# 7_High_Voltage.net
KiCad netlist of a schematic drawn in Altium Designer
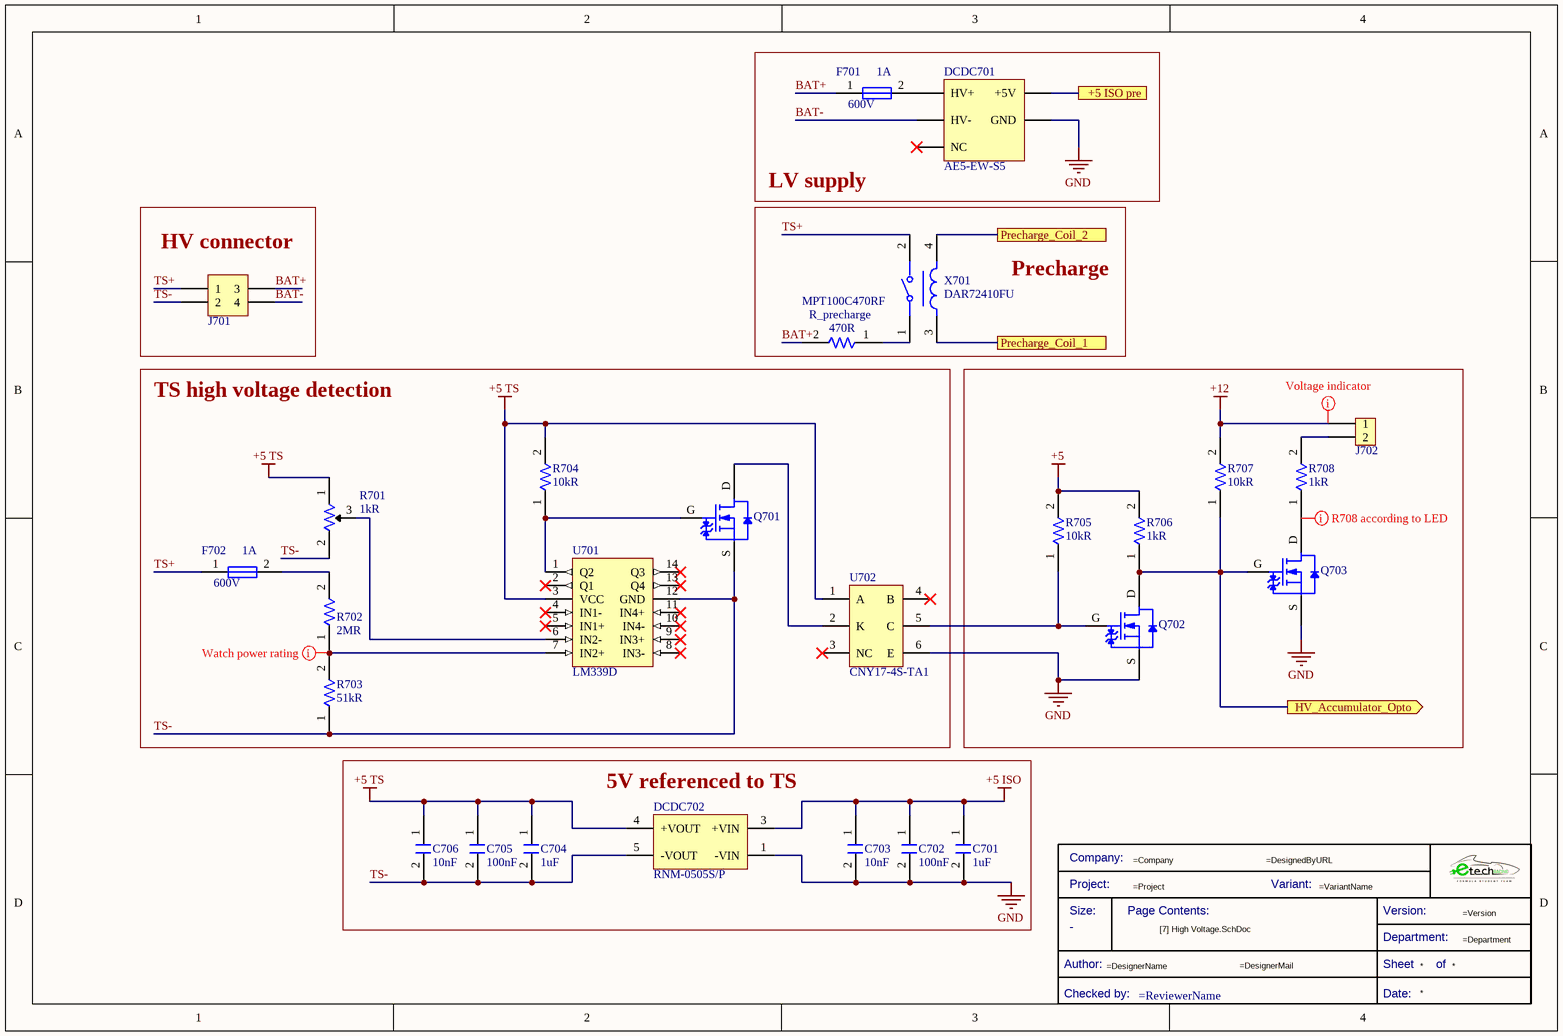
[diagram p0: [7] High Voltage.SchDoc]

(export (version "E")
  (design (tool "Eeschema 10.0.6"))
  (components
    (comp (ref "*")
      (value "Title Block_template")
      (description "Standard Title Block")
      (fields (field (name "SIZE") "-"))
      (libsource (lib "e-Tech_Racing") (part "Title Block_template"))
    )
    (comp (ref "C701")
      (value "885012207103")
      (footprint "C0805FNPC-R")
      (fields
        (field (name "TOLERANCE") "10%")
        (field (name "CAPACITANCE") "1uF")
        (field (name ".CREATOR") "GP")
      )
      (libsource (lib "Passives") (part "C1u-50V-0805FNPC-X7R"))
    )
    (comp (ref "C702")
      (value "885012207098")
      (footprint "C0805FNPC-R")
      (description "Cap, 0.1ΜF, 50V, 10%, X7R, 0805")
      (fields
        (field (name "TOLERANCE") "10%")
        (field (name "CAPACITANCE") "100nF")
        (field (name ".CREATOR") "DR")
      )
      (libsource (lib "Passives") (part "C100n-50V-0805FNPC-X7R"))
    )
    (comp (ref "C703")
      (value "885012207092")
      (footprint "C0805FNPC-R")
      (description "Cap, 0.01ΜF, 50V, 10%, X7R, 0805")
      (fields
        (field (name "TOLERANCE") "10%")
        (field (name "CAPACITANCE") "10nF")
        (field (name ".CREATOR") "DR")
      )
      (libsource (lib "Passives") (part "C10n-50V-0805FNPC-X7R"))
    )
    (comp (ref "C704")
      (value "885012207103")
      (footprint "C0805FNPC-R")
      (fields
        (field (name "TOLERANCE") "10%")
        (field (name "CAPACITANCE") "1uF")
        (field (name ".CREATOR") "GP")
      )
      (libsource (lib "Passives") (part "C1u-50V-0805FNPC-X7R"))
    )
    (comp (ref "C705")
      (value "885012207098")
      (footprint "C0805FNPC-R")
      (description "Cap, 0.1ΜF, 50V, 10%, X7R, 0805")
      (fields
        (field (name "TOLERANCE") "10%")
        (field (name "CAPACITANCE") "100nF")
        (field (name ".CREATOR") "DR")
      )
      (libsource (lib "Passives") (part "C100n-50V-0805FNPC-X7R"))
    )
    (comp (ref "C706")
      (value "885012207092")
      (footprint "C0805FNPC-R")
      (description "Cap, 0.01ΜF, 50V, 10%, X7R, 0805")
      (fields
        (field (name "TOLERANCE") "10%")
        (field (name "CAPACITANCE") "10nF")
        (field (name ".CREATOR") "DR")
      )
      (libsource (lib "Passives") (part "C10n-50V-0805FNPC-X7R"))
    )
    (comp (ref "DCDC701")
      (value "AE5-EW-S5")
      (footprint "DCDC_1000-5_ISO")
      (description "dc-dc isolated, 5 W, 100~1000 Vdc input, 5V, 1 A, DIP, ext temp")
      (fields (field (name "MANUFACTURER PART NUMBER 1") "AE5-EW-S5") (field (name ".CREATOR") "DR"))
      (libsource (lib "Semiconductor") (part "DCDC-ISO-1000V/5V-1A"))
    )
    (comp (ref "DCDC702")
      (value "RNM-0505S/P")
      (footprint "DCDC_RNM-0505S/P")
      (description "1W DC/DC-Converter 'ECONOLINE' DIP6 1kV unreg; V. In: 05; V. Out: 05; mA. Out: 200")
      (fields
        (field (name "MANUFACTURER") "Recom")
        (field (name "MANUFACTURER PART NUMBER") "RNM-0505S/P")
        (field (name ".CREATOR") "GP")
      )
      (libsource (lib "Semiconductor") (part "DCDC_RNM-0505S/P"))
    )
    (comp (ref "F701")
      (value "485001")
      (footprint "Fuse_485001")
      (description "Surface Mount Fuses 600V 1A Fast Acting")
      (fields
        (field (name "VOLTAGE RATING (DC)") "600V")
        (field (name "CURRENT RATING") "1A")
        (field (name ".CREATOR") "DO")
      )
      (libsource (lib "Filter components") (part "Fuse_1A_600V"))
    )
    (comp (ref "F702")
      (value "485001")
      (footprint "Fuse_485001")
      (description "Surface Mount Fuses 600V 1A Fast Acting")
      (fields
        (field (name "VOLTAGE RATING (DC)") "600V")
        (field (name "CURRENT RATING") "1A")
        (field (name ".CREATOR") "DO")
      )
      (libsource (lib "Filter components") (part "Fuse_1A_600V"))
    )
    (comp (ref "J701")
      (value "430450412")
      (footprint "J_MicroFit_2x2_v")
      (description "Header 2 Row Vertical Polarizing Peg 4 Pin Tin Plate SMT/Glow Wire Kinked Leads")
      (fields (field (name ".CREATOR") "DR"))
      (libsource (lib "Electromechanical") (part "J_MicroFit_2x2"))
    )
    (comp (ref "J702")
      (value "282836-2")
      (footprint "J_screw_1x2")
      (description "Connector, Terminal Block; Wire Receptacle; 2 Pos.; 16-30 AWG; 0.197 in. CL; Sid")
      (libsource (lib "Electromechanical") (part "J_CON2x1"))
    )
    (comp (ref "Q701")
      (value "CPH3455-TL-H")
      (footprint "TRT-NCH-3/35-CPH")
      (description "CPH3455-TL-H N-channel MOSFET Transistor; 3 A; 35 V; 3-Pin CPH")
      (fields (field (name "MANUFACTURER") "ON Semiconductor") (field (name ".CREATOR") "GP"))
      (libsource (lib "Semiconductor") (part "TRT-NCH-3/35-CPH"))
    )
    (comp (ref "Q702")
      (value "CPH3455-TL-H")
      (footprint "TRT-NCH-3/35-CPH")
      (description "CPH3455-TL-H N-channel MOSFET Transistor; 3 A; 35 V; 3-Pin CPH")
      (fields (field (name "MANUFACTURER") "ON Semiconductor") (field (name ".CREATOR") "GP"))
      (libsource (lib "Semiconductor") (part "TRT-NCH-3/35-CPH"))
    )
    (comp (ref "Q703")
      (value "CPH3455-TL-H")
      (footprint "TRT-NCH-3/35-CPH")
      (description "CPH3455-TL-H N-channel MOSFET Transistor; 3 A; 35 V; 3-Pin CPH")
      (fields (field (name "MANUFACTURER") "ON Semiconductor") (field (name ".CREATOR") "GP"))
      (libsource (lib "Semiconductor") (part "TRT-NCH-3/35-CPH"))
    )
    (comp (ref "R701")
      (value "3296Y-1-102LF")
      (footprint "R1k-VTR")
      (description "Res Cermet Trimmer 1K Ohm 10% 1/2W 25(Elec)Turn 2.19mm (9.53 X 4.83 X 11.55mm) Pin Thru-Hole Tube")
      (fields
        (field (name "MANUFACTURER") "Bourns")
        (field (name "TOLERANCE") "10%")
        (field (name "RESISTANCE") "1kR")
        (field (name ".CREATOR") "DO")
      )
      (libsource (lib "Passives") (part "R1k-VTR"))
    )
    (comp (ref "R702")
      (value "HVC1206-2M0FT3")
      (footprint "R1206FTK-W")
      (description "Res Thick Film 1206 2M Ohm 1% 0.3W ±100ppm/C Pad SMD T/R")
      (fields
        (field (name "MANUFACTURER") "TT Welwyn")
        (field (name "TOLERANCE") "1%")
        (field (name "RESISTENCE") "2MR")
        (field (name ".CREATOR") "DO")
      )
      (libsource (lib "Passives") (part "R2M-1206FTK"))
    )
    (comp (ref "R703")
      (value "CRCW120610K0FKEA")
      (footprint "R1206FTK-W")
      (description "Res Thick Film 1206 51K Ohm 1% 1/4W ±100ppm/°C Molded SMD SMD Punched Carrier T/R")
      (fields
        (field (name "MANUFACTURER") "Panasonic")
        (field (name "MANUFACTURER PART NUMBER") "ERJ-S08F5102V")
        (field (name "RESISTANCE") "51kR")
        (field (name ".CREATOR") "DO")
      )
      (libsource (lib "Passives") (part "R51k-1206FTK"))
    )
    (comp (ref "R704")
      (value "CR0805-JW-103ELF")
      (footprint "R0805FTK")
      (fields
        (field (name "TOLERANCE") "5%")
        (field (name "RESISTANCE") "10kR")
        (field (name ".CREATOR") "DR")
      )
      (libsource (lib "Passives") (part "R10k-0805FTK"))
    )
    (comp (ref "R705")
      (value "CR0805-JW-103ELF")
      (footprint "R0805FTK")
      (fields
        (field (name "TOLERANCE") "5%")
        (field (name "RESISTANCE") "10kR")
        (field (name ".CREATOR") "DR")
      )
      (libsource (lib "Passives") (part "R10k-0805FTK"))
    )
    (comp (ref "R706")
      (value "CR0805-JW-102ELF")
      (footprint "R0805FTK")
      (description "Res Thick Film 0805 1K Ohm 5% 1/8W ±200ppm/°C Molded SMD SMD Paper Tape on Plastic Reel")
      (fields
        (field (name "TOLERANCE") "5%")
        (field (name "RESISTANCE") "1kR")
        (field (name ".CREATOR") "GP")
      )
      (libsource (lib "Passives") (part "R1k-0805FTK"))
    )
    (comp (ref "R707")
      (value "CR0805-JW-103ELF")
      (footprint "R0805FTK")
      (fields
        (field (name "TOLERANCE") "5%")
        (field (name "RESISTANCE") "10kR")
        (field (name ".CREATOR") "DR")
      )
      (libsource (lib "Passives") (part "R10k-0805FTK"))
    )
    (comp (ref "R708")
      (value "CR0805-JW-102ELF")
      (footprint "R0805FTK")
      (description "Res Thick Film 0805 1K Ohm 5% 1/8W ±200ppm/°C Molded SMD SMD Paper Tape on Plastic Reel")
      (fields
        (field (name "TOLERANCE") "5%")
        (field (name "RESISTANCE") "1kR")
        (field (name ".CREATOR") "GP")
      )
      (libsource (lib "Passives") (part "R1k-0805FTK"))
    )
    (comp (ref "R_precharge")
      (value "R470-TO220")
      (fields
        (field (name "MANUFACTURER") "TE Connectivity")
        (field (name "MANUFACTURER PART NUMBER") "MPT100C470RF")
        (field (name "RESISTANCE") "470R")
      )
      (libsource (lib "Passives") (part "R470-TO220"))
    )
    (comp (ref "U701")
      (value "LM339D")
      (footprint "Array_4_Amp_LM339D")
      (description "Comparator Quad ±18V/36V 14-Pin SOIC Tube")
      (fields
        (field (name "MANUFACTURER") "Texas Instruments")
        (field (name "MANUFACTURER PART NUMBER") "LM339D")
        (field (name ".CREATOR") "DO")
      )
      (libsource (lib "Integrated circuits") (part "Array_4_Amp_LM339D"))
    )
    (comp (ref "U702")
      (value "4N35")
      (footprint "Optocoupler_4N35")
      (description "Optocoupler DC-IN 1-CH Transistor With Base DC-OUT 6-Pin PDIP SMD T/R")
      (fields
        (field (name "MANUFACTURER") "Vishay Lite-On")
        (field (name "MANUFACTURER PART NUMBER") "CNY17-4S-TA1")
        (field (name ".CREATOR") "DO")
      )
      (libsource (lib "Semiconductor") (part "Optocoupler_4N35"))
    )
    (comp (ref "X701")
      (value "DAR72410FU")
      (footprint "Relay_DAR72410FU")
      (description "Relay; Reed; SPST N/O 10kV Isolation 24V Coil (Flying Lead) UL")
      (fields (field (name "MANUFACTURER") "Cynergy3") (field (name "MANUFACTURER PART NUMBER") "DAR72410FU"))
      (libsource (lib "Electromechanical") (part "Relay_DAR72410FU"))
    )
  )
  (nets
    (net (code "1") (name "+5") (class "Default")
      (node (ref "R705") (pin "2") (pinfunction "2_2") (pintype "passive"))
      (node (ref "R706") (pin "2") (pinfunction "2_2") (pintype "passive"))
    )
    (net (code "2") (name "+5 ISO") (class "Default")
      (node (ref "C701") (pin "1") (pinfunction "1_1") (pintype "passive"))
      (node (ref "C702") (pin "1") (pinfunction "1_1") (pintype "passive"))
      (node (ref "C703") (pin "1") (pinfunction "1_1") (pintype "passive"))
      (node (ref "DCDC702") (pin "3") (pinfunction "+VIN_3") (pintype "passive"))
    )
    (net (code "3") (name "+5 TS") (class "Default")
      (node (ref "C704") (pin "1") (pinfunction "1_1") (pintype "passive"))
      (node (ref "C705") (pin "1") (pinfunction "1_1") (pintype "passive"))
      (node (ref "C706") (pin "1") (pinfunction "1_1") (pintype "passive"))
      (node (ref "DCDC702") (pin "4") (pinfunction "+VOUT_4") (pintype "passive"))
      (node (ref "R701") (pin "1") (pinfunction "2_1") (pintype "passive"))
      (node (ref "R704") (pin "2") (pinfunction "2_2") (pintype "passive"))
      (node (ref "U701") (pin "3") (pinfunction "VCC_3") (pintype "power_in"))
      (node (ref "U702") (pin "1") (pinfunction "A_1") (pintype "passive"))
    )
    (net (code "4") (name "+12") (class "Default")
      (node (ref "J702") (pin "1") (pinfunction "1_1") (pintype "passive"))
      (node (ref "R707") (pin "2") (pinfunction "2_2") (pintype "passive"))
    )
    (net (code "5") (name "/+5 ISO pre") (class "Default")
      (node (ref "DCDC701") (pin "4") (pinfunction "+5V_4") (pintype "passive"))
    )
    (net (code "6") (name "/BAT+") (class "Default")
      (node (ref "F701") (pin "1") (pinfunction "1_1") (pintype "passive"))
      (node (ref "J701") (pin "3") (pinfunction "3_3") (pintype "passive"))
      (node (ref "R_precharge") (pin "2") (pinfunction "2_2") (pintype "passive"))
    )
    (net (code "7") (name "/BAT-") (class "Default")
      (node (ref "DCDC701") (pin "2") (pinfunction "HV-_2") (pintype "passive"))
      (node (ref "J701") (pin "4") (pinfunction "4_4") (pintype "passive"))
    )
    (net (code "8") (name "/HV_Accumulator_Opto") (class "Default")
      (node (ref "Q702") (pin "D") (pinfunction "D_D") (pintype "passive"))
      (node (ref "Q703") (pin "G") (pinfunction "G_G") (pintype "passive"))
      (node (ref "R706") (pin "1") (pinfunction "1_1") (pintype "passive"))
      (node (ref "R707") (pin "1") (pinfunction "1_1") (pintype "passive"))
    )
    (net (code "9") (name "/Precharge_Coil_1") (class "Default")
      (node (ref "X701") (pin "3") (pinfunction "3_3") (pintype "passive"))
    )
    (net (code "10") (name "/Precharge_Coil_2") (class "Default")
      (node (ref "X701") (pin "4") (pinfunction "4_4") (pintype "passive"))
    )
    (net (code "11") (name "/TS+") (class "Default")
      (node (ref "F702") (pin "1") (pinfunction "1_1") (pintype "passive"))
      (node (ref "J701") (pin "1") (pinfunction "1_1") (pintype "passive"))
      (node (ref "X701") (pin "2") (pinfunction "2_2") (pintype "passive"))
    )
    (net (code "12") (name "/TS-") (class "Default")
      (node (ref "C704") (pin "2") (pinfunction "2_2") (pintype "passive"))
      (node (ref "C705") (pin "2") (pinfunction "2_2") (pintype "passive"))
      (node (ref "C706") (pin "2") (pinfunction "2_2") (pintype "passive"))
      (node (ref "DCDC702") (pin "5") (pinfunction "-VOUT_5") (pintype "passive"))
      (node (ref "J701") (pin "2") (pinfunction "2_2") (pintype "passive"))
      (node (ref "Q701") (pin "S") (pinfunction "S_S") (pintype "passive"))
      (node (ref "R701") (pin "2") (pinfunction "2_2") (pintype "passive"))
      (node (ref "R703") (pin "1") (pinfunction "1_1") (pintype "passive"))
      (node (ref "U701") (pin "12") (pinfunction "GND_12") (pintype "power_in"))
    )
    (net (code "13") (name "GND") (class "Default")
      (node (ref "C701") (pin "2") (pinfunction "2_2") (pintype "passive"))
      (node (ref "C702") (pin "2") (pinfunction "2_2") (pintype "passive"))
      (node (ref "C703") (pin "2") (pinfunction "2_2") (pintype "passive"))
      (node (ref "DCDC701") (pin "5") (pinfunction "GND_5") (pintype "passive"))
      (node (ref "DCDC702") (pin "1") (pinfunction "-VIN_1") (pintype "passive"))
      (node (ref "Q702") (pin "S") (pinfunction "S_S") (pintype "passive"))
      (node (ref "Q703") (pin "S") (pinfunction "S_S") (pintype "passive"))
      (node (ref "U702") (pin "6") (pinfunction "E_6") (pintype "passive"))
    )
    (net (code "14") (name "Net-(DCDC701-HV+)") (class "Default")
      (node (ref "DCDC701") (pin "3") (pinfunction "HV+_3") (pintype "passive"))
      (node (ref "F701") (pin "2") (pinfunction "2_2") (pintype "passive"))
    )
    (net (code "15") (name "Net-(F702-Pad2)") (class "Default")
      (node (ref "F702") (pin "2") (pinfunction "2_2") (pintype "passive"))
      (node (ref "R702") (pin "2") (pinfunction "2_2") (pintype "passive"))
    )
    (net (code "16") (name "Net-(J702-Pad2)") (class "Default")
      (node (ref "J702") (pin "2") (pinfunction "2_2") (pintype "passive"))
      (node (ref "R708") (pin "2") (pinfunction "2_2") (pintype "passive"))
    )
    (net (code "17") (name "Net-(Q703-PadD)") (class "Default")
      (node (ref "Q703") (pin "D") (pinfunction "D_D") (pintype "passive"))
      (node (ref "R708") (pin "1") (pinfunction "1_1") (pintype "passive"))
    )
    (net (code "18") (name "Net-(R_precharge-Pad1)") (class "Default")
      (node (ref "R_precharge") (pin "1") (pinfunction "1_1") (pintype "passive"))
      (node (ref "X701") (pin "1") (pinfunction "1_1") (pintype "passive"))
    )
    (net (code "19") (name "Net-(U701-IN2+)") (class "Default")
      (node (ref "R702") (pin "1") (pinfunction "1_1") (pintype "passive"))
      (node (ref "R703") (pin "2") (pinfunction "2_2") (pintype "passive"))
      (node (ref "U701") (pin "7") (pinfunction "IN2+_7") (pintype "input"))
    )
    (net (code "20") (name "Net-(U701-IN2-)") (class "Default")
      (node (ref "R701") (pin "3") (pinfunction "3_3") (pintype "passive"))
      (node (ref "U701") (pin "6") (pinfunction "IN2-_6") (pintype "input"))
    )
    (net (code "21") (name "Net-(U701-Q2)") (class "Default")
      (node (ref "Q701") (pin "G") (pinfunction "G_G") (pintype "passive"))
      (node (ref "R704") (pin "1") (pinfunction "1_1") (pintype "passive"))
      (node (ref "U701") (pin "1") (pinfunction "Q2_1") (pintype "output"))
    )
    (net (code "22") (name "Net-(U702-C)") (class "Default")
      (node (ref "Q702") (pin "G") (pinfunction "G_G") (pintype "passive"))
      (node (ref "R705") (pin "1") (pinfunction "1_1") (pintype "passive"))
      (node (ref "U702") (pin "5") (pinfunction "C_5") (pintype "passive"))
    )
    (net (code "23") (name "Net-(U702-K)") (class "Default")
      (node (ref "Q701") (pin "D") (pinfunction "D_D") (pintype "passive"))
      (node (ref "U702") (pin "2") (pinfunction "K_2") (pintype "passive"))
    )
    (net (code "24") (name "unconnected-(DCDC701-NC-Pad1)") (class "Default")
      (node (ref "DCDC701") (pin "1") (pinfunction "NC_1") (pintype "passive+no_connect"))
    )
    (net (code "25") (name "unconnected-(U701-IN1+-Pad5)") (class "Default")
      (node (ref "U701") (pin "5") (pinfunction "IN1+_5") (pintype "input+no_connect"))
    )
    (net (code "26") (name "unconnected-(U701-IN1--Pad4)") (class "Default")
      (node (ref "U701") (pin "4") (pinfunction "IN1-_4") (pintype "input+no_connect"))
    )
    (net (code "27") (name "unconnected-(U701-IN3+-Pad9)") (class "Default")
      (node (ref "U701") (pin "9") (pinfunction "IN3+_9") (pintype "input+no_connect"))
    )
    (net (code "28") (name "unconnected-(U701-IN3--Pad8)") (class "Default")
      (node (ref "U701") (pin "8") (pinfunction "IN3-_8") (pintype "input+no_connect"))
    )
    (net (code "29") (name "unconnected-(U701-IN4+-Pad11)") (class "Default")
      (node (ref "U701") (pin "11") (pinfunction "IN4+_11") (pintype "input+no_connect"))
    )
    (net (code "30") (name "unconnected-(U701-IN4--Pad10)") (class "Default")
      (node (ref "U701") (pin "10") (pinfunction "IN4-_10") (pintype "input+no_connect"))
    )
    (net (code "31") (name "unconnected-(U701-Q1-Pad2)") (class "Default")
      (node (ref "U701") (pin "2") (pinfunction "Q1_2") (pintype "output+no_connect"))
    )
    (net (code "32") (name "unconnected-(U701-Q3-Pad14)") (class "Default")
      (node (ref "U701") (pin "14") (pinfunction "Q3_14") (pintype "output+no_connect"))
    )
    (net (code "33") (name "unconnected-(U701-Q4-Pad13)") (class "Default")
      (node (ref "U701") (pin "13") (pinfunction "Q4_13") (pintype "output+no_connect"))
    )
    (net (code "34") (name "unconnected-(U702-B-Pad4)") (class "Default")
      (node (ref "U702") (pin "4") (pinfunction "B_4") (pintype "passive+no_connect"))
    )
    (net (code "35") (name "unconnected-(U702-NC-Pad3)") (class "Default")
      (node (ref "U702") (pin "3") (pinfunction "NC_3") (pintype "passive+no_connect"))
    )
  )
)
